# MDQARM_POWER.net
KiCad netlist of a schematic drawn in Altium Designer
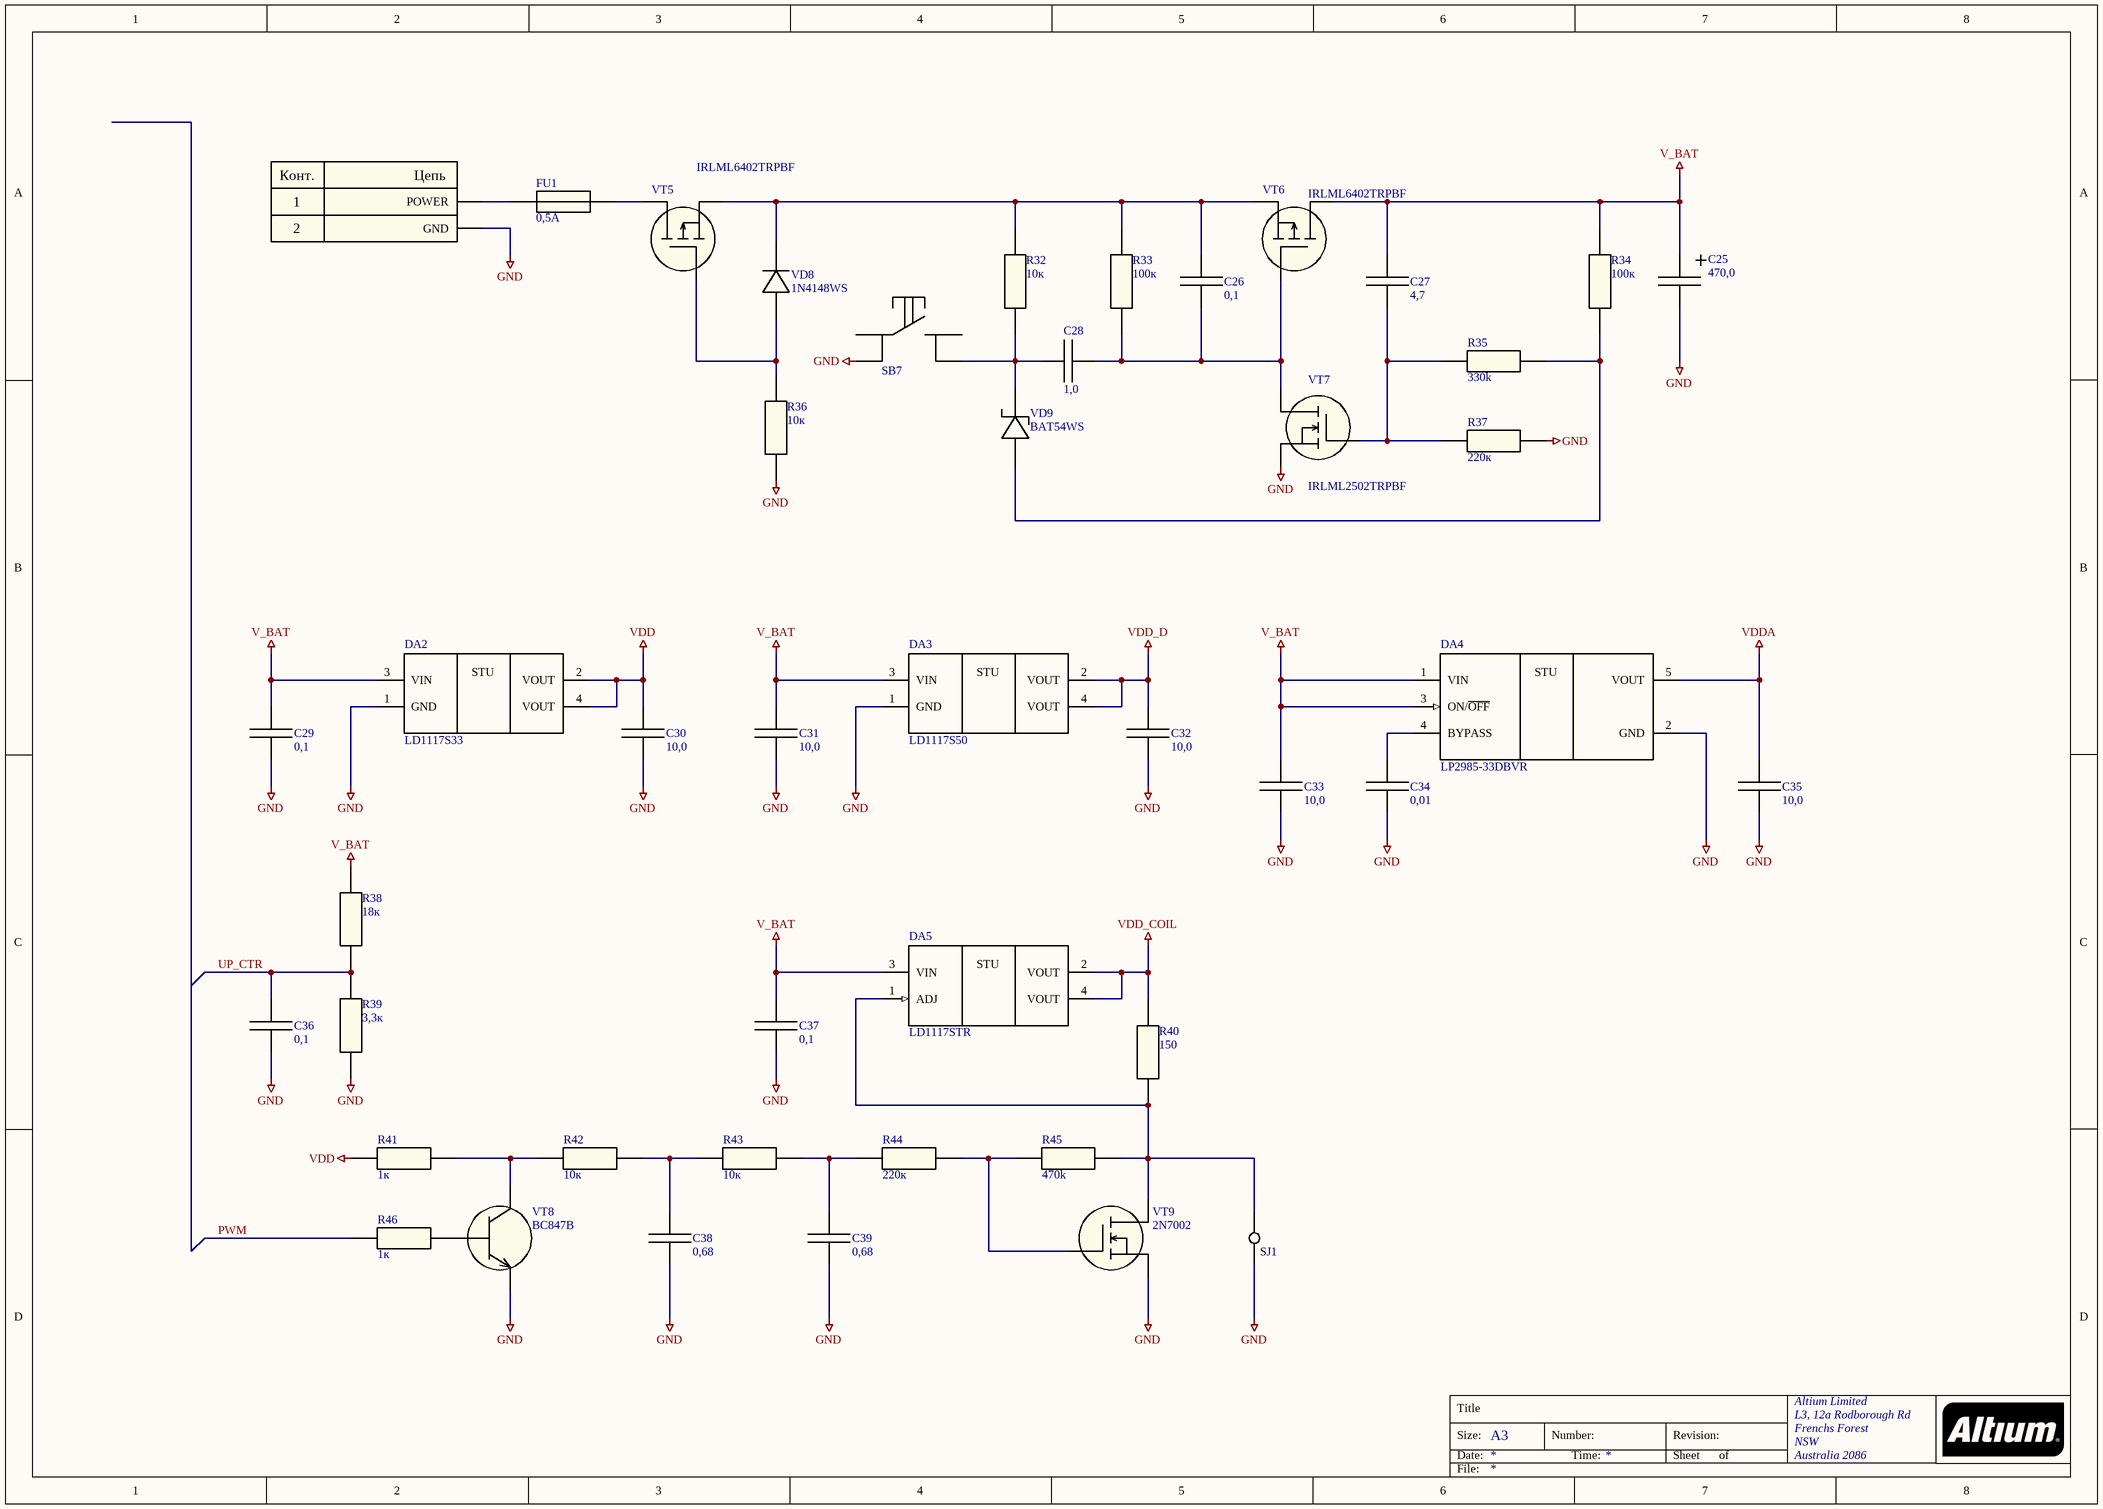
[diagram p0: MDQARM_POWER.SchDoc]

(export (version "E")
  (design (tool "Eeschema 10.0.6"))
  (components
    (comp (ref "*2")
      (value "Connector MD_POWER")
      (footprint "Connector MD_POWER")
      (libsource (lib "IVV_Connectors") (part "Connector MD_POWER"))
    )
    (comp (ref "C25")
      (value "470,0")
      (footprint "Capacitor ECAP SMD10x10.5")
      (libsource (lib "IVV_Passive") (part "Capacitor ECAP SMD 470uF_16V"))
    )
    (comp (ref "C26")
      (value "0,1")
      (footprint "Capacitor SMD0805-T0.95")
      (libsource (lib "IVV_Passive") (part "Capacitor C0805_100n"))
    )
    (comp (ref "C27")
      (value "4,7")
      (footprint "Capacitor SMD0805-T1.35")
      (libsource (lib "IVV_Passive") (part "Capacitor C0805_4.7u"))
    )
    (comp (ref "C28")
      (value "1,0")
      (footprint "Capacitor SMD0805-T1.35")
      (libsource (lib "IVV_Passive") (part "Capacitor C0805_1u"))
    )
    (comp (ref "C29")
      (value "0,1")
      (footprint "Capacitor SMD0805-T0.95")
      (libsource (lib "IVV_Passive") (part "Capacitor C0805_100n"))
    )
    (comp (ref "C30")
      (value "10,0")
      (footprint "Capacitor SMD0805-T1.35")
      (libsource (lib "IVV_Passive") (part "Capacitor C0805_10u"))
    )
    (comp (ref "C31")
      (value "10,0")
      (footprint "Capacitor SMD0805-T1.35")
      (libsource (lib "IVV_Passive") (part "Capacitor C0805_10u"))
    )
    (comp (ref "C32")
      (value "10,0")
      (footprint "Capacitor SMD0805-T1.35")
      (libsource (lib "IVV_Passive") (part "Capacitor C0805_10u"))
    )
    (comp (ref "C33")
      (value "10,0")
      (footprint "Capacitor SMD0805-T1.35")
      (libsource (lib "IVV_Passive") (part "Capacitor C0805_10u"))
    )
    (comp (ref "C34")
      (value "0,01")
      (footprint "Capacitor SMD0805-T0.75")
      (libsource (lib "IVV_Passive") (part "Capacitor C0805_10n"))
    )
    (comp (ref "C35")
      (value "10,0")
      (footprint "Capacitor SMD0805-T1.35")
      (libsource (lib "IVV_Passive") (part "Capacitor C0805_10u"))
    )
    (comp (ref "C36")
      (value "0,1")
      (footprint "Capacitor SMD0805-T0.95")
      (libsource (lib "IVV_Passive") (part "Capacitor C0805_100n"))
    )
    (comp (ref "C37")
      (value "0,1")
      (footprint "Capacitor SMD0805-T0.95")
      (libsource (lib "IVV_Passive") (part "Capacitor C0805_100n"))
    )
    (comp (ref "C38")
      (value "0,68")
      (footprint "Capacitor SMD0805-T0.95")
      (libsource (lib "IVV_Passive") (part "Capacitor C0805_680n"))
    )
    (comp (ref "C39")
      (value "0,68")
      (footprint "Capacitor SMD0805-T0.95")
      (libsource (lib "IVV_Passive") (part "Capacitor C0805_680n"))
    )
    (comp (ref "DA2")
      (value "LD1117S33")
      (footprint "IC LD1117S33")
      (libsource (lib "IVV_IC") (part "IC LD1117S33"))
    )
    (comp (ref "DA3")
      (value "LD1117S50")
      (footprint "IC LD1117S50")
      (libsource (lib "IVV_IC") (part "IC LD1117S50"))
    )
    (comp (ref "DA4")
      (value "LP2985-33DBVR")
      (footprint "IC LP2985-33DBVR")
      (libsource (lib "IVV_IC") (part "IC LP2985-33DBVR"))
    )
    (comp (ref "DA5")
      (value "LD1117STR")
      (footprint "IC LD1117STR")
      (libsource (lib "IVV_IC") (part "IC LD1117STR"))
    )
    (comp (ref "FU1")
      (value "0,5А")
      (footprint "Fuse MF-NSMF")
      (libsource (lib "IVV_Lib") (part "Fuse MF-NSMF050-2"))
    )
    (comp (ref "R32")
      (value "10к")
      (footprint "Resistor SMD0805")
      (libsource (lib "IVV_Passive") (part "Resistor R0805_10k_5%"))
    )
    (comp (ref "R33")
      (value "100к")
      (footprint "Resistor SMD0805")
      (libsource (lib "IVV_Passive") (part "Resistor R0805_100k_5%"))
    )
    (comp (ref "R34")
      (value "100к")
      (footprint "Resistor SMD0805")
      (libsource (lib "IVV_Passive") (part "Resistor R0805_100k_5%"))
    )
    (comp (ref "R35")
      (value "330k")
      (footprint "Resistor SMD0805")
      (libsource (lib "IVV_Passive") (part "Resistor R0805_330k_5%"))
    )
    (comp (ref "R36")
      (value "10к")
      (footprint "Resistor SMD0805")
      (libsource (lib "IVV_Passive") (part "Resistor R0805_10k_5%"))
    )
    (comp (ref "R37")
      (value "220к")
      (footprint "Resistor SMD0805")
      (libsource (lib "IVV_Passive") (part "Resistor R0805_220k_5%"))
    )
    (comp (ref "R38")
      (value "18к")
      (footprint "Resistor SMD0805")
      (libsource (lib "IVV_Passive") (part "Resistor R0805_18k_5%"))
    )
    (comp (ref "R39")
      (value "3,3к")
      (footprint "Resistor SMD0805")
      (libsource (lib "IVV_Passive") (part "Resistor R0805_3.3k_5%"))
    )
    (comp (ref "R40")
      (value "150")
      (footprint "Resistor SMD0805")
      (libsource (lib "IVV_Passive") (part "Resistor R0805_150_5%"))
    )
    (comp (ref "R41")
      (value "1к")
      (footprint "Resistor SMD0805")
      (libsource (lib "IVV_Passive") (part "Resistor R0805_1k_5%"))
    )
    (comp (ref "R42")
      (value "10к")
      (footprint "Resistor SMD0805")
      (libsource (lib "") (part "Resistor R0805_10k_5%_1"))
    )
    (comp (ref "R43")
      (value "10к")
      (footprint "Resistor SMD0805")
      (libsource (lib "") (part "Resistor R0805_10k_5%_1"))
    )
    (comp (ref "R44")
      (value "220к")
      (footprint "Resistor SMD0805")
      (libsource (lib "IVV_Passive") (part "Resistor R0805_220k_5%"))
    )
    (comp (ref "R45")
      (value "470k")
      (footprint "Resistor SMD0805")
      (libsource (lib "IVV_Passive") (part "Resistor R0805_470k_5%"))
    )
    (comp (ref "R46")
      (value "1к")
      (footprint "Resistor SMD0805")
      (libsource (lib "IVV_Passive") (part "Resistor R0805_1k_5%"))
    )
    (comp (ref "SB7")
      (value "KLS7-TS6604-4.3-180")
      (footprint "Button KLS7-TS6604-4.3-180")
      (description "SMD Tact Switch 4.3mm")
      (libsource (lib "IVV_Lib") (part "Button KLS7-TS6604-4.3-180"))
    )
    (comp (ref "SJ1")
      (value "SolderJump 1")
      (footprint "SolderJump 1")
      (libsource (lib "IVV_Lib") (part "SolderJump 1"))
    )
    (comp (ref "VD8")
      (value "1N4148WS")
      (footprint "Diode SOD-323")
      (description "150mA 100V 4ns")
      (libsource (lib "IVV_Lib") (part "Diode 1N4148WS"))
    )
    (comp (ref "VD9")
      (value "BAT54WS")
      (footprint "Diode SOD-323")
      (description "200mA 30V Schottky")
      (libsource (lib "IVV_Lib") (part "Diode BAT54WS"))
    )
    (comp (ref "VT5")
      (value "IRLML6402TRPBF")
      (footprint "Transistor SOT23")
      (libsource (lib "IVV_Lib") (part "Transistor IRLML6402TRPBF"))
    )
    (comp (ref "VT6")
      (value "IRLML6402TRPBF")
      (footprint "Transistor SOT23")
      (libsource (lib "IVV_Lib") (part "Transistor IRLML6402TRPBF"))
    )
    (comp (ref "VT7")
      (value "IRLML2502TRPBF")
      (footprint "Transistor SOT23")
      (libsource (lib "IVV_Lib") (part "Transistor IRLML2502TRPBF"))
    )
    (comp (ref "VT8")
      (value "BC847B")
      (footprint "Transistor SOT23")
      (libsource (lib "IVV_Lib") (part "Transistor BC847B"))
    )
    (comp (ref "VT9")
      (value "2N7002")
      (footprint "Transistor SOT23")
      (libsource (lib "IVV_Lib") (part "Transistor 2N7002"))
    )
  )
  (nets
    (net (code "1") (name "/PWM") (class "Default")
      (node (ref "R46") (pin "1") (pinfunction "1_1") (pintype "passive"))
    )
    (net (code "2") (name "/UP_CTR") (class "Default")
      (node (ref "C36") (pin "2") (pinfunction "2_2") (pintype "passive"))
      (node (ref "R38") (pin "1") (pinfunction "1_1") (pintype "passive"))
      (node (ref "R39") (pin "2") (pinfunction "2_2") (pintype "passive"))
    )
    (net (code "3") (name "GND") (class "Default")
      (node (ref "*2") (pin "2") (pinfunction "GND_2") (pintype "passive"))
      (node (ref "C25") (pin "2") (pinfunction "2_2") (pintype "passive"))
      (node (ref "C29") (pin "1") (pinfunction "1_1") (pintype "passive"))
      (node (ref "C30") (pin "1") (pinfunction "1_1") (pintype "passive"))
      (node (ref "C31") (pin "1") (pinfunction "1_1") (pintype "passive"))
      (node (ref "C32") (pin "1") (pinfunction "1_1") (pintype "passive"))
      (node (ref "C33") (pin "1") (pinfunction "1_1") (pintype "passive"))
      (node (ref "C34") (pin "1") (pinfunction "1_1") (pintype "passive"))
      (node (ref "C35") (pin "1") (pinfunction "1_1") (pintype "passive"))
      (node (ref "C36") (pin "1") (pinfunction "1_1") (pintype "passive"))
      (node (ref "C37") (pin "1") (pinfunction "1_1") (pintype "passive"))
      (node (ref "C38") (pin "1") (pinfunction "1_1") (pintype "passive"))
      (node (ref "C39") (pin "1") (pinfunction "1_1") (pintype "passive"))
      (node (ref "DA2") (pin "1") (pinfunction "GND_1") (pintype "power_in"))
      (node (ref "DA3") (pin "1") (pinfunction "GND_1") (pintype "power_in"))
      (node (ref "DA4") (pin "2") (pinfunction "GND_2") (pintype "power_in"))
      (node (ref "R36") (pin "1") (pinfunction "1_1") (pintype "passive"))
      (node (ref "R37") (pin "2") (pinfunction "2_2") (pintype "passive"))
      (node (ref "R39") (pin "1") (pinfunction "1_1") (pintype "passive"))
      (node (ref "SB7") (pin "2") (pinfunction "2_2") (pintype "passive"))
      (node (ref "SJ1") (pin "1") (pinfunction "1_1") (pintype "passive"))
      (node (ref "VT7") (pin "2") (pinfunction "S_2") (pintype "passive"))
      (node (ref "VT8") (pin "2") (pinfunction "E_2") (pintype "passive"))
      (node (ref "VT9") (pin "2") (pinfunction "S_2") (pintype "passive"))
    )
    (net (code "4") (name "Net-(*2-POWER)") (class "Default")
      (node (ref "*2") (pin "1") (pinfunction "POWER_1") (pintype "passive"))
      (node (ref "FU1") (pin "1") (pinfunction "1_1") (pintype "passive"))
    )
    (net (code "5") (name "Net-(C38-Pad2)") (class "Default")
      (node (ref "C38") (pin "2") (pinfunction "2_2") (pintype "passive"))
      (node (ref "R42") (pin "2") (pinfunction "2_2") (pintype "passive"))
      (node (ref "R43") (pin "1") (pinfunction "1_1") (pintype "passive"))
    )
    (net (code "6") (name "Net-(C39-Pad2)") (class "Default")
      (node (ref "C39") (pin "2") (pinfunction "2_2") (pintype "passive"))
      (node (ref "R43") (pin "2") (pinfunction "2_2") (pintype "passive"))
      (node (ref "R44") (pin "1") (pinfunction "1_1") (pintype "passive"))
    )
    (net (code "7") (name "Net-(DA4-BYPASS)") (class "Default")
      (node (ref "C34") (pin "2") (pinfunction "2_2") (pintype "passive"))
      (node (ref "DA4") (pin "4") (pinfunction "BYPASS_4") (pintype "passive"))
    )
    (net (code "8") (name "Net-(DA5-ADJ)") (class "Default")
      (node (ref "DA5") (pin "1") (pinfunction "ADJ_1") (pintype "input"))
      (node (ref "R40") (pin "2") (pinfunction "2_2") (pintype "passive"))
      (node (ref "R45") (pin "2") (pinfunction "2_2") (pintype "passive"))
      (node (ref "SJ1") (pin "2") (pinfunction "2_2") (pintype "passive"))
      (node (ref "VT9") (pin "3") (pinfunction "D_3") (pintype "passive"))
    )
    (net (code "9") (name "Net-(VD8-A)") (class "Default")
      (node (ref "R36") (pin "2") (pinfunction "2_2") (pintype "passive"))
      (node (ref "VD8") (pin "1") (pinfunction "A_1") (pintype "passive"))
      (node (ref "VT5") (pin "1") (pinfunction "G_1") (pintype "passive"))
    )
    (net (code "10") (name "Net-(VD8-C)") (class "Default")
      (node (ref "C26") (pin "2") (pinfunction "2_2") (pintype "passive"))
      (node (ref "R32") (pin "2") (pinfunction "2_2") (pintype "passive"))
      (node (ref "R33") (pin "2") (pinfunction "2_2") (pintype "passive"))
      (node (ref "VD8") (pin "2") (pinfunction "C_2") (pintype "passive"))
      (node (ref "VT5") (pin "2") (pinfunction "S_2") (pintype "passive"))
      (node (ref "VT6") (pin "2") (pinfunction "S_2") (pintype "passive"))
    )
    (net (code "11") (name "Net-(VD9-A)") (class "Default")
      (node (ref "R34") (pin "1") (pinfunction "1_1") (pintype "passive"))
      (node (ref "R35") (pin "2") (pinfunction "2_2") (pintype "passive"))
      (node (ref "VD9") (pin "1") (pinfunction "A_1") (pintype "passive"))
    )
    (net (code "12") (name "Net-(VD9-C)") (class "Default")
      (node (ref "C28") (pin "1") (pinfunction "1_1") (pintype "passive"))
      (node (ref "R32") (pin "1") (pinfunction "1_1") (pintype "passive"))
      (node (ref "SB7") (pin "3") (pinfunction "3_3") (pintype "passive"))
      (node (ref "VD9") (pin "2") (pinfunction "C_2") (pintype "passive"))
    )
    (net (code "13") (name "Net-(VT5-D)") (class "Default")
      (node (ref "FU1") (pin "2") (pinfunction "2_2") (pintype "passive"))
      (node (ref "VT5") (pin "3") (pinfunction "D_3") (pintype "passive"))
    )
    (net (code "14") (name "Net-(VT6-G)") (class "Default")
      (node (ref "C26") (pin "1") (pinfunction "1_1") (pintype "passive"))
      (node (ref "C28") (pin "2") (pinfunction "2_2") (pintype "passive"))
      (node (ref "R33") (pin "1") (pinfunction "1_1") (pintype "passive"))
      (node (ref "VT6") (pin "1") (pinfunction "G_1") (pintype "passive"))
      (node (ref "VT7") (pin "3") (pinfunction "D_3") (pintype "passive"))
    )
    (net (code "15") (name "Net-(VT7-G)") (class "Default")
      (node (ref "C27") (pin "1") (pinfunction "1_1") (pintype "passive"))
      (node (ref "R35") (pin "1") (pinfunction "1_1") (pintype "passive"))
      (node (ref "R37") (pin "1") (pinfunction "1_1") (pintype "passive"))
      (node (ref "VT7") (pin "1") (pinfunction "G_1") (pintype "passive"))
    )
    (net (code "16") (name "Net-(VT8-B)") (class "Default")
      (node (ref "R46") (pin "2") (pinfunction "2_2") (pintype "passive"))
      (node (ref "VT8") (pin "1") (pinfunction "B_1") (pintype "passive"))
    )
    (net (code "17") (name "Net-(VT8-C)") (class "Default")
      (node (ref "R41") (pin "2") (pinfunction "2_2") (pintype "passive"))
      (node (ref "R42") (pin "1") (pinfunction "1_1") (pintype "passive"))
      (node (ref "VT8") (pin "3") (pinfunction "C_3") (pintype "passive"))
    )
    (net (code "18") (name "Net-(VT9-G)") (class "Default")
      (node (ref "R44") (pin "2") (pinfunction "2_2") (pintype "passive"))
      (node (ref "R45") (pin "1") (pinfunction "1_1") (pintype "passive"))
      (node (ref "VT9") (pin "1") (pinfunction "G_1") (pintype "passive"))
    )
    (net (code "19") (name "VDD") (class "Default")
      (node (ref "C30") (pin "2") (pinfunction "2_2") (pintype "passive"))
      (node (ref "DA2") (pin "2") (pinfunction "VOUT_2") (pintype "power_in"))
      (node (ref "DA2") (pin "4") (pinfunction "VOUT_4") (pintype "power_in"))
      (node (ref "R41") (pin "1") (pinfunction "1_1") (pintype "passive"))
    )
    (net (code "20") (name "VDDA") (class "Default")
      (node (ref "C35") (pin "2") (pinfunction "2_2") (pintype "passive"))
      (node (ref "DA4") (pin "5") (pinfunction "VOUT_5") (pintype "power_in"))
    )
    (net (code "21") (name "VDD_COIL") (class "Default")
      (node (ref "DA5") (pin "2") (pinfunction "VOUT_2") (pintype "power_in"))
      (node (ref "DA5") (pin "4") (pinfunction "VOUT_4") (pintype "power_in"))
      (node (ref "R40") (pin "1") (pinfunction "1_1") (pintype "passive"))
    )
    (net (code "22") (name "VDD_D") (class "Default")
      (node (ref "C32") (pin "2") (pinfunction "2_2") (pintype "passive"))
      (node (ref "DA3") (pin "2") (pinfunction "VOUT_2") (pintype "power_in"))
      (node (ref "DA3") (pin "4") (pinfunction "VOUT_4") (pintype "power_in"))
    )
    (net (code "23") (name "V_BAT") (class "Default")
      (node (ref "C25") (pin "1") (pinfunction "1_1") (pintype "passive"))
      (node (ref "C27") (pin "2") (pinfunction "2_2") (pintype "passive"))
      (node (ref "C29") (pin "2") (pinfunction "2_2") (pintype "passive"))
      (node (ref "C31") (pin "2") (pinfunction "2_2") (pintype "passive"))
      (node (ref "C33") (pin "2") (pinfunction "2_2") (pintype "passive"))
      (node (ref "C37") (pin "2") (pinfunction "2_2") (pintype "passive"))
      (node (ref "DA2") (pin "3") (pinfunction "VIN_3") (pintype "power_in"))
      (node (ref "DA3") (pin "3") (pinfunction "VIN_3") (pintype "power_in"))
      (node (ref "DA4") (pin "1") (pinfunction "VIN_1") (pintype "power_in"))
      (node (ref "DA4") (pin "3") (pinfunction "ON/~{OFF}_3") (pintype "input"))
      (node (ref "DA5") (pin "3") (pinfunction "VIN_3") (pintype "power_in"))
      (node (ref "R34") (pin "2") (pinfunction "2_2") (pintype "passive"))
      (node (ref "R38") (pin "2") (pinfunction "2_2") (pintype "passive"))
      (node (ref "VT6") (pin "3") (pinfunction "D_3") (pintype "passive"))
    )
    (net (code "24") (name "unconnected-(SB7-Pad1)") (class "Default")
      (node (ref "SB7") (pin "1") (pinfunction "1_1") (pintype "passive"))
    )
    (net (code "25") (name "unconnected-(SB7-Pad4)") (class "Default")
      (node (ref "SB7") (pin "4") (pinfunction "4_4") (pintype "passive"))
    )
  )
)
